# OMODRI_Gate_Driver_2.net
KiCad netlist of a schematic drawn in Altium Designer
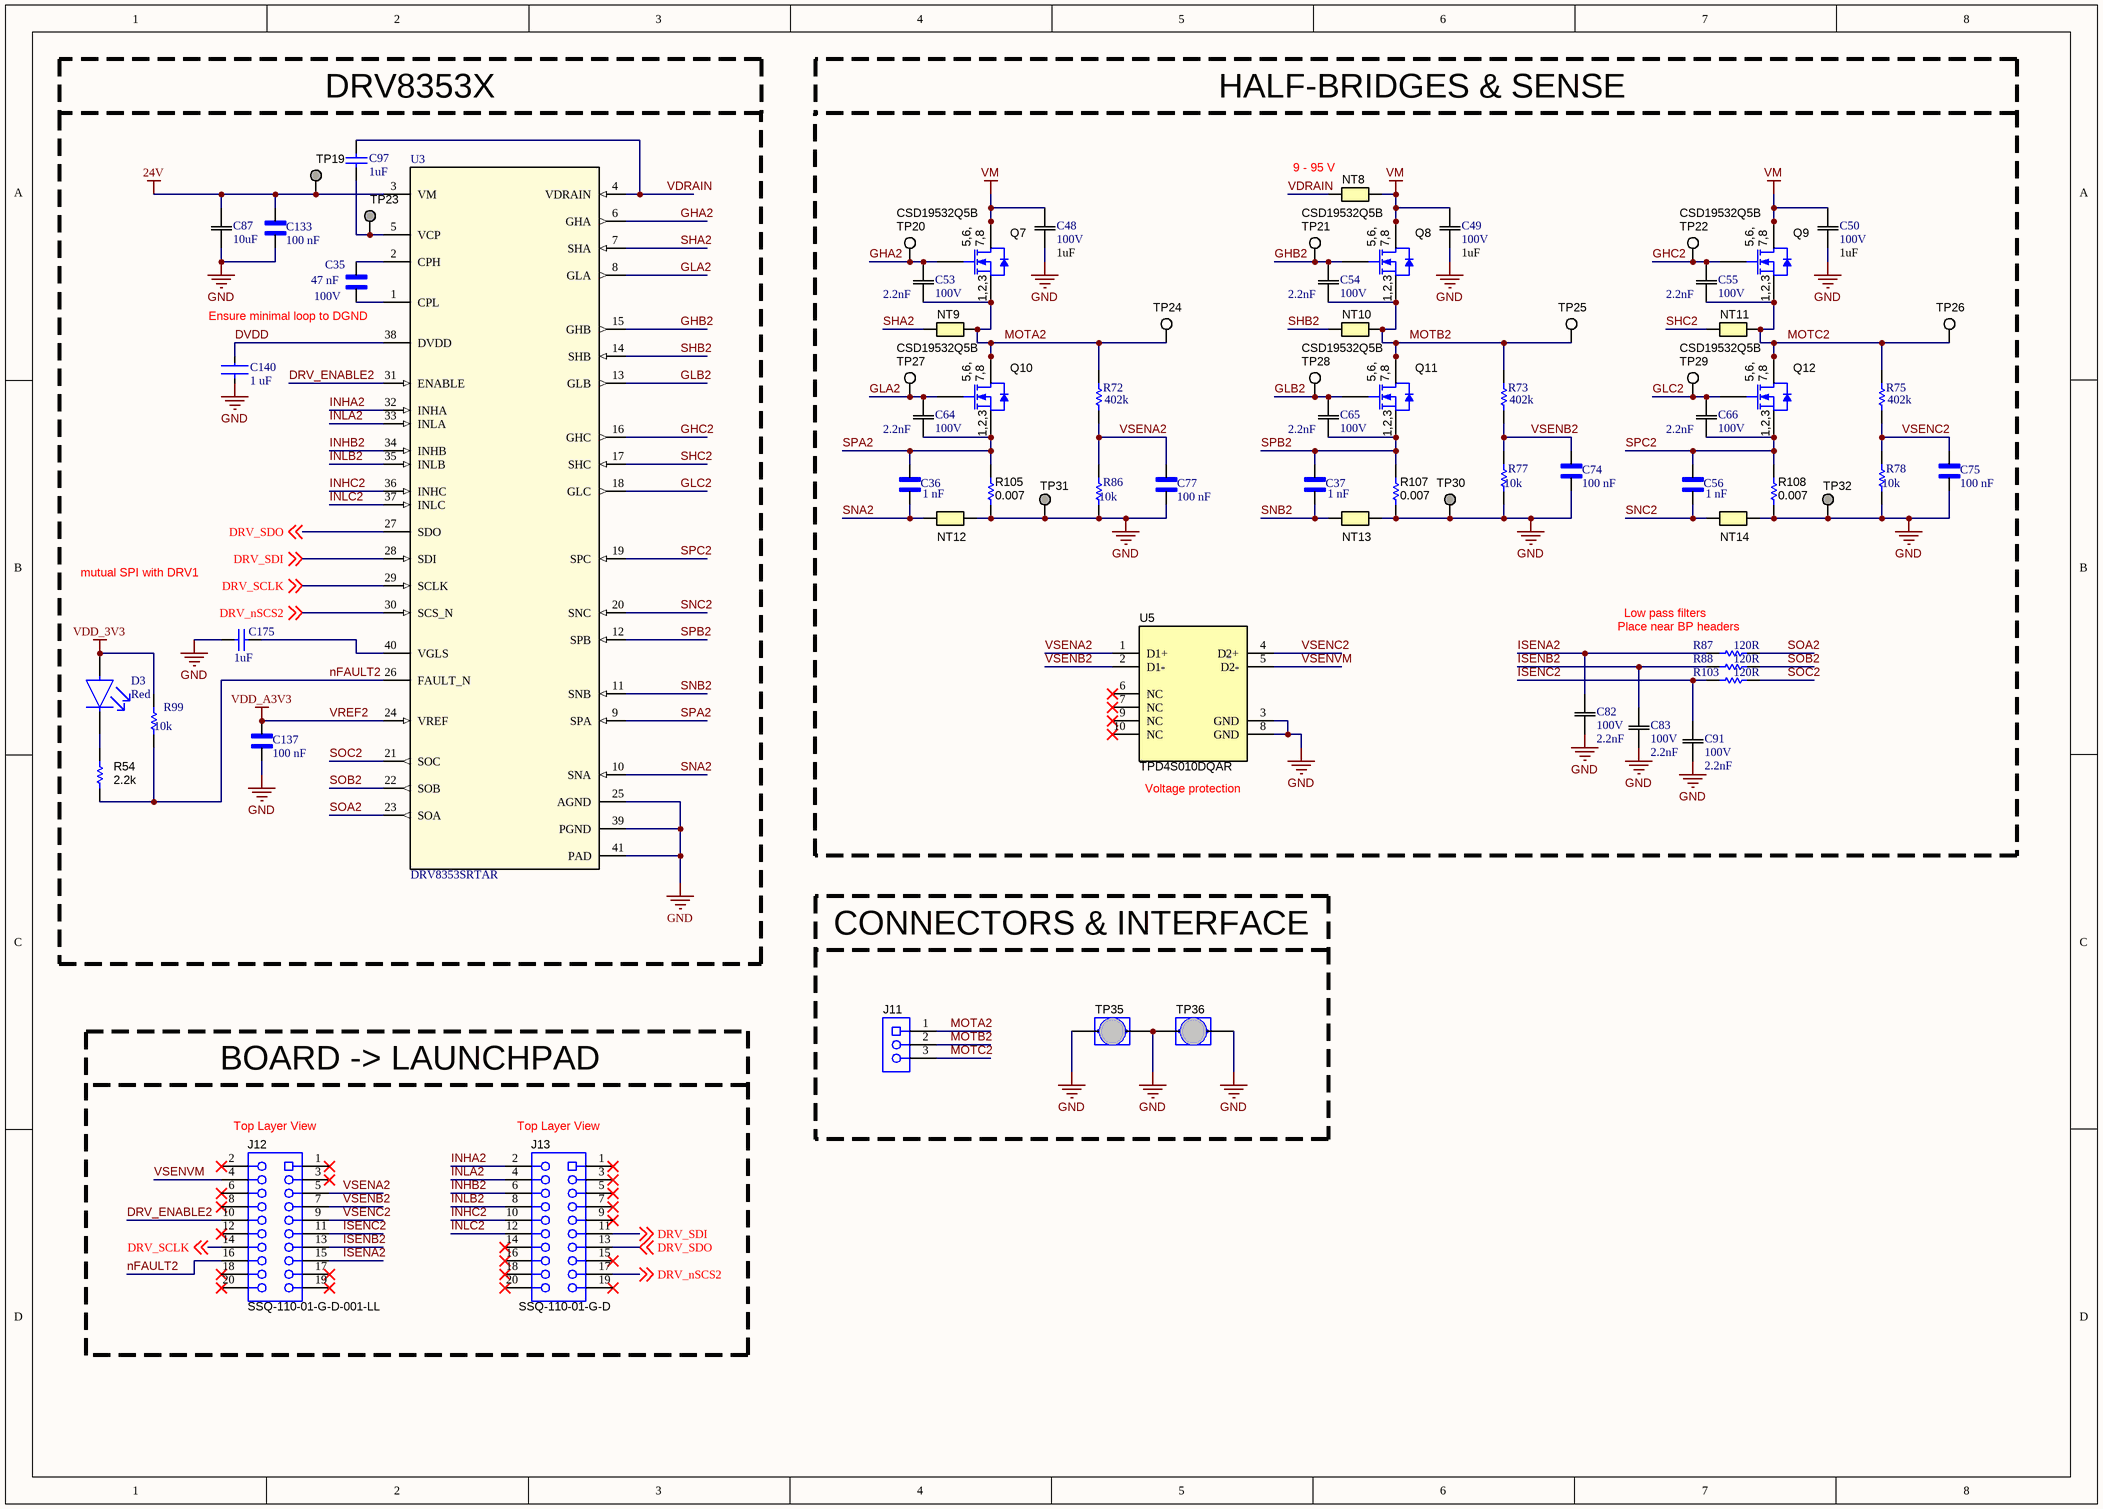
[diagram p0: OMODRI_Gate_Driver_2.SchDoc]

(export (version "E")
  (design (tool "Eeschema 10.0.6"))
  (components
    (comp (ref "C35")
      (value "47 nF")
      (footprint "CAPC1608X90N")
      (description "SMD Capacitor X8R_EIA_ with Capacitance: 47000pF Tol. 10%. Rated Voltage: 100Vdc")
      (fields
        (field (name "DIGI-KEY_PART_NUMBER") "490-GCG188R92A473KA01DCT-ND")
        (field (name "MP") "GCG188R92A473KA01D")
        (field (name "VOLTAGE") "100V")
      )
      (libsource (lib "Murata-Capacitor") (part "GCG188R92A473KA01D"))
    )
    (comp (ref "C36")
      (value "1 nF")
      (footprint "CAPC0603X33N")
      (description "SMD Capacitor X7R_EIA_ with Capacitance: 1000pF Tol. 10%. Rated Voltage: 50Vdc")
      (fields (field (name "DIGI-KEY_PART_NUMBER") "490-10682-1-ND") (field (name "MP") "GRM033R71H102KA12D"))
      (libsource (lib "Murata-CapacitorGRM") (part "GRM033R71H102KA12D"))
    )
    (comp (ref "C37")
      (value "1 nF")
      (footprint "CAPC0603X33N")
      (description "SMD Capacitor X7R_EIA_ with Capacitance: 1000pF Tol. 10%. Rated Voltage: 50Vdc")
      (fields (field (name "DIGI-KEY_PART_NUMBER") "490-10682-1-ND") (field (name "MP") "GRM033R71H102KA12D"))
      (libsource (lib "Murata-CapacitorGRM") (part "GRM033R71H102KA12D"))
    )
    (comp (ref "C48")
      (value "1uF")
      (footprint "0805_AVX")
      (description "Cap Ceramic 1uF 100V X7R 10% Pad SMD 0805 Soft Termination 125C Automotive T/R")
      (fields
        (field (name "MANUFACTURER_PART_NUMBER") "08051C102K4Z2A")
        (field (name "MANUFACTURER") "Kyocera AVX")
        (field (name "VOLTAGE") "100V")
        (field (name "COPYRIGHT") "Copyright (C) 2018 Accelerated Designs. All rights reserved")
      )
      (libsource (lib "AVX-Capacitor") (part "08051C105K4Z2A"))
    )
    (comp (ref "C49")
      (value "1uF")
      (footprint "0805_AVX")
      (description "Cap Ceramic 1uF 100V X7R 10% Pad SMD 0805 Soft Termination 125C Automotive T/R")
      (fields
        (field (name "MANUFACTURER_PART_NUMBER") "08051C102K4Z2A")
        (field (name "MANUFACTURER") "Kyocera AVX")
        (field (name "VOLTAGE") "100V")
        (field (name "COPYRIGHT") "Copyright (C) 2018 Accelerated Designs. All rights reserved")
      )
      (libsource (lib "AVX-Capacitor") (part "08051C105K4Z2A"))
    )
    (comp (ref "C50")
      (value "1uF")
      (footprint "0805_AVX")
      (description "Cap Ceramic 1uF 100V X7R 10% Pad SMD 0805 Soft Termination 125C Automotive T/R")
      (fields
        (field (name "MANUFACTURER_PART_NUMBER") "08051C102K4Z2A")
        (field (name "MANUFACTURER") "Kyocera AVX")
        (field (name "VOLTAGE") "100V")
        (field (name "COPYRIGHT") "Copyright (C) 2018 Accelerated Designs. All rights reserved")
      )
      (libsource (lib "AVX-Capacitor") (part "08051C105K4Z2A"))
    )
    (comp (ref "C53")
      (value "Part Number: C1005X8R2A222K050BA")
      (footprint "CAP_1005")
      (description "CAP CER 2200PF 100V X8R 0402")
      (fields
        (field (name "MANUFACTURER_PART_NUMBER") "C1005X8R2A222K050BA")
        (field (name "MANUFACTURER") "TDK")
        (field (name "VOLTAGE RATING (DC)") "100V")
        (field (name "CAPACITANCE") "2.2nF")
        (field (name "COPYRIGHT") "Copyright (C) 2018 Accelerated Designs. All rights reserved")
      )
      (libsource (lib "TDK-Capacitor") (part "C1005X8R2A222K05"))
    )
    (comp (ref "C54")
      (value "Part Number: C1005X8R2A222K050BA")
      (footprint "CAP_1005")
      (description "CAP CER 2200PF 100V X8R 0402")
      (fields
        (field (name "MANUFACTURER_PART_NUMBER") "C1005X8R2A222K050BA")
        (field (name "MANUFACTURER") "TDK")
        (field (name "VOLTAGE RATING (DC)") "100V")
        (field (name "CAPACITANCE") "2.2nF")
        (field (name "COPYRIGHT") "Copyright (C) 2018 Accelerated Designs. All rights reserved")
      )
      (libsource (lib "TDK-Capacitor") (part "C1005X8R2A222K05"))
    )
    (comp (ref "C55")
      (value "Part Number: C1005X8R2A222K050BA")
      (footprint "CAP_1005")
      (description "CAP CER 2200PF 100V X8R 0402")
      (fields
        (field (name "MANUFACTURER_PART_NUMBER") "C1005X8R2A222K050BA")
        (field (name "MANUFACTURER") "TDK")
        (field (name "VOLTAGE RATING (DC)") "100V")
        (field (name "CAPACITANCE") "2.2nF")
        (field (name "COPYRIGHT") "Copyright (C) 2018 Accelerated Designs. All rights reserved")
      )
      (libsource (lib "TDK-Capacitor") (part "C1005X8R2A222K05"))
    )
    (comp (ref "C56")
      (value "1 nF")
      (footprint "CAPC0603X33N")
      (description "SMD Capacitor X7R_EIA_ with Capacitance: 1000pF Tol. 10%. Rated Voltage: 50Vdc")
      (fields (field (name "DIGI-KEY_PART_NUMBER") "490-10682-1-ND") (field (name "MP") "GRM033R71H102KA12D"))
      (libsource (lib "Murata-CapacitorGRM") (part "GRM033R71H102KA12D"))
    )
    (comp (ref "C64")
      (value "Part Number: C1005X8R2A222K050BA")
      (footprint "CAP_1005")
      (description "CAP CER 2200PF 100V X8R 0402")
      (fields
        (field (name "MANUFACTURER_PART_NUMBER") "C1005X8R2A222K050BA")
        (field (name "MANUFACTURER") "TDK")
        (field (name "VOLTAGE RATING (DC)") "100V")
        (field (name "CAPACITANCE") "2.2nF")
        (field (name "COPYRIGHT") "Copyright (C) 2018 Accelerated Designs. All rights reserved")
      )
      (libsource (lib "TDK-Capacitor") (part "C1005X8R2A222K05"))
    )
    (comp (ref "C65")
      (value "Part Number: C1005X8R2A222K050BA")
      (footprint "CAP_1005")
      (description "CAP CER 2200PF 100V X8R 0402")
      (fields
        (field (name "MANUFACTURER_PART_NUMBER") "C1005X8R2A222K050BA")
        (field (name "MANUFACTURER") "TDK")
        (field (name "VOLTAGE RATING (DC)") "100V")
        (field (name "CAPACITANCE") "2.2nF")
        (field (name "COPYRIGHT") "Copyright (C) 2018 Accelerated Designs. All rights reserved")
      )
      (libsource (lib "TDK-Capacitor") (part "C1005X8R2A222K05"))
    )
    (comp (ref "C66")
      (value "Part Number: C1005X8R2A222K050BA")
      (footprint "CAP_1005")
      (description "CAP CER 2200PF 100V X8R 0402")
      (fields
        (field (name "MANUFACTURER_PART_NUMBER") "C1005X8R2A222K050BA")
        (field (name "MANUFACTURER") "TDK")
        (field (name "VOLTAGE RATING (DC)") "100V")
        (field (name "CAPACITANCE") "2.2nF")
        (field (name "COPYRIGHT") "Copyright (C) 2018 Accelerated Designs. All rights reserved")
      )
      (libsource (lib "TDK-Capacitor") (part "C1005X8R2A222K05"))
    )
    (comp (ref "C74")
      (value "100 nF")
      (footprint "CAPC0603X33N")
      (description "SMD Capacitor X5R_EIA_ with Capacitance: 0.10uF Tol. 10%. Rated Voltage: 25Vdc")
      (fields (field (name "MF") "Murata") (field (name "MP") "GRM033R61E104KE14D"))
      (libsource (lib "GRM033R61E104KE14D") (part "GRM033R61E104KE14D"))
    )
    (comp (ref "C75")
      (value "100 nF")
      (footprint "CAPC0603X33N")
      (description "SMD Capacitor X5R_EIA_ with Capacitance: 0.10uF Tol. 10%. Rated Voltage: 25Vdc")
      (fields (field (name "MF") "Murata") (field (name "MP") "GRM033R61E104KE14D"))
      (libsource (lib "GRM033R61E104KE14D") (part "GRM033R61E104KE14D"))
    )
    (comp (ref "C77")
      (value "100 nF")
      (footprint "CAPC0603X33N")
      (description "SMD Capacitor X5R_EIA_ with Capacitance: 0.10uF Tol. 10%. Rated Voltage: 25Vdc")
      (fields (field (name "MF") "Murata") (field (name "MP") "GRM033R61E104KE14D"))
      (libsource (lib "GRM033R61E104KE14D") (part "GRM033R61E104KE14D"))
    )
    (comp (ref "C82")
      (value "Part Number: C1005X8R2A222K050BA")
      (footprint "CAP_1005")
      (description "CAP CER 2200PF 100V X8R 0402")
      (fields
        (field (name "MANUFACTURER_PART_NUMBER") "C1005X8R2A222K050BA")
        (field (name "MANUFACTURER") "TDK")
        (field (name "VOLTAGE RATING (DC)") "100V")
        (field (name "CAPACITANCE") "2.2nF")
        (field (name "COPYRIGHT") "Copyright (C) 2018 Accelerated Designs. All rights reserved")
      )
      (libsource (lib "TDK-Capacitor") (part "C1005X8R2A222K05"))
    )
    (comp (ref "C83")
      (value "Part Number: C1005X8R2A222K050BA")
      (footprint "CAP_1005")
      (description "CAP CER 2200PF 100V X8R 0402")
      (fields
        (field (name "MANUFACTURER_PART_NUMBER") "C1005X8R2A222K050BA")
        (field (name "MANUFACTURER") "TDK")
        (field (name "VOLTAGE RATING (DC)") "100V")
        (field (name "CAPACITANCE") "2.2nF")
        (field (name "COPYRIGHT") "Copyright (C) 2018 Accelerated Designs. All rights reserved")
      )
      (libsource (lib "TDK-Capacitor") (part "C1005X8R2A222K05"))
    )
    (comp (ref "C87")
      (value "Part Number: CL10A106MA8NRNC")
      (footprint "CAP_CL10")
      (description "CAP CER 10UF 25V X5R 0603")
      (fields
        (field (name "MANUFACTURER_PART_NUMBER") "CL10A106MA8NRNC")
        (field (name "MANUFACTURER") "Samsung")
        (field (name "CAPACITANCE") "10uF")
        (field (name "COPYRIGHT") "Copyright (C) 2018 Accelerated Designs. All rights reserved")
      )
      (libsource (lib "Samsung-Capacitor") (part "CL10A106MA8NRNC"))
    )
    (comp (ref "C91")
      (value "Part Number: C1005X8R2A222K050BA")
      (footprint "CAP_1005")
      (description "CAP CER 2200PF 100V X8R 0402")
      (fields
        (field (name "MANUFACTURER_PART_NUMBER") "C1005X8R2A222K050BA")
        (field (name "MANUFACTURER") "TDK")
        (field (name "VOLTAGE RATING (DC)") "100V")
        (field (name "CAPACITANCE") "2.2nF")
        (field (name "COPYRIGHT") "Copyright (C) 2018 Accelerated Designs. All rights reserved")
      )
      (libsource (lib "TDK-Capacitor") (part "C1005X8R2A222K05"))
    )
    (comp (ref "C97")
      (value "1uF")
      (footprint "CAPC1005X55X25ML05T10")
      (fields (field (name "PART NUMBER") "GRM155R61C105KA12D") (field (name "MANUFACTURER") "Murata"))
      (libsource (lib "Altium Content Vault") (part "CAP"))
    )
    (comp (ref "C133")
      (value "100 nF")
      (footprint "CAPC0603X33N")
      (description "SMD Capacitor X5R_EIA_ with Capacitance: 0.10uF Tol. 10%. Rated Voltage: 25Vdc")
      (fields (field (name "MF") "Murata") (field (name "MP") "GRM033R61E104KE14D"))
      (libsource (lib "GRM033R61E104KE14D") (part "GRM033R61E104KE14D"))
    )
    (comp (ref "C137")
      (value "100 nF")
      (footprint "CAPC0603X33N")
      (description "SMD Capacitor X5R_EIA_ with Capacitance: 0.10uF Tol. 10%. Rated Voltage: 25Vdc")
      (fields (field (name "MF") "Murata") (field (name "MP") "GRM033R61E104KE14D"))
      (libsource (lib "GRM033R61E104KE14D") (part "GRM033R61E104KE14D"))
    )
    (comp (ref "C140")
      (value "1 uF")
      (footprint "FP-CC0201-BA-MFG")
      (description "CAP CER 1UF 6.3V X5R 0201")
      (fields (field (name "TOLERANCE") "0.2") (field (name "MANUFACTURER") "Yageo"))
      (libsource (lib "Altium Content Vault") (part "11868f565c42a9108669ba33697ecf6"))
    )
    (comp (ref "C175")
      (value "1uF")
      (footprint "CAPC1005X55X25ML05T10")
      (fields (field (name "PART NUMBER") "GRM155R61C105KA12D") (field (name "MANUFACTURER") "Murata"))
      (libsource (lib "Altium Content Vault") (part "CAP"))
    )
    (comp (ref "D3")
      (value "SML-P11UTT86R")
      (footprint "FP-SML-P1-MFG")
      (description "LED, PICOLED, Red, SMD, 1 mA, 1.8 V, 621 nm")
      (fields
        (field (name "MANUFACTURER PART NUMBER") "SML-P11VTT86R")
        (field (name "OCTOPART") "https://octopart.com/sml-p11vtt86r-rohm-34112314")
        (field (name "COLOUR") "Red")
      )
      (libsource (lib "LED") (part "SML-P11UTT86R"))
    )
    (comp (ref "J11")
      (value "1904150")
      (footprint "Phoenix_1904150")
      (description "Terminal Block, 9.52mm, 3x1, R/A, TH")
      (fields (field (name "MANUFACTURER") "Phoenix Contact") (field (name "PUBLISHER") "Texas Instruments"))
      (libsource (lib "Altium Vault - TI") (part "Receptacle_3x1"))
    )
    (comp (ref "J12")
      (value "SSQ-110-01-G-D-001-LL")
      (footprint "Samtec_SSQ-110-01-x-D-001-LL")
      (description "Receptacle, 2.54mm, 10x2, Gold, TH")
      (fields (field (name "MANUFACTURER") "Samtec"))
      (libsource (lib "Altium Vault - TI") (part "Receptacle_10x2"))
    )
    (comp (ref "J13")
      (value "SSQ-110-01-G-D")
      (footprint "Samtec_SSQ-110-01-x-D")
      (description "Receptacle, 2.54mm, 10x2, Gold, TH")
      (fields (field (name "MANUFACTURER") "Samtec"))
      (libsource (lib "Altium Vault - TI") (part "CMP-0082605-1"))
    )
    (comp (ref "NT8")
      (value "Net-Tie")
      (footprint "Net-Tie_50milWide_30milLong")
      (description "Single point connection between nets.")
      (libsource (lib "Altium Vault - TI") (part "Net-Tie"))
    )
    (comp (ref "NT9")
      (value "Net-Tie")
      (footprint "Net-Tie_10mil")
      (description "Single point connection between nets.")
      (libsource (lib "Altium Vault - TI") (part "Net-Tie"))
    )
    (comp (ref "NT10")
      (value "Net-Tie")
      (footprint "Net-Tie_10mil")
      (description "Single point connection between nets.")
      (libsource (lib "Altium Vault - TI") (part "Net-Tie"))
    )
    (comp (ref "NT11")
      (value "Net-Tie")
      (footprint "Net-Tie_10mil")
      (description "Single point connection between nets.")
      (libsource (lib "Altium Vault - TI") (part "Net-Tie"))
    )
    (comp (ref "NT12")
      (value "Net-Tie")
      (footprint "Net-Tie_10mil")
      (description "Single point connection between nets.")
      (libsource (lib "Altium Vault - TI") (part "Net-Tie"))
    )
    (comp (ref "NT13")
      (value "Net-Tie")
      (footprint "Net-Tie_10mil")
      (description "Single point connection between nets.")
      (libsource (lib "Altium Vault - TI") (part "Net-Tie"))
    )
    (comp (ref "NT14")
      (value "Net-Tie")
      (footprint "Net-Tie_10mil")
      (description "Single point connection between nets.")
      (libsource (lib "Altium Vault - TI") (part "Net-Tie"))
    )
    (comp (ref "Q7")
      (value "CSD19532Q5B")
      (footprint "DNK0008A")
      (description "MOSFET, N-CH, 100 V, 17 A, DNK0008A (VSON-CLIP-8)")
      (fields (field (name "MANUFACTURER") "Texas Instruments"))
      (libsource (lib "Altium Vault - TI") (part "MOSFET_N_D56789G4S123"))
    )
    (comp (ref "Q8")
      (value "CSD19532Q5B")
      (footprint "DNK0008A")
      (description "MOSFET, N-CH, 100 V, 17 A, DNK0008A (VSON-CLIP-8)")
      (fields (field (name "MANUFACTURER") "Texas Instruments"))
      (libsource (lib "Altium Vault - TI") (part "MOSFET_N_D56789G4S123"))
    )
    (comp (ref "Q9")
      (value "CSD19532Q5B")
      (footprint "DNK0008A")
      (description "MOSFET, N-CH, 100 V, 17 A, DNK0008A (VSON-CLIP-8)")
      (fields (field (name "MANUFACTURER") "Texas Instruments"))
      (libsource (lib "Altium Vault - TI") (part "MOSFET_N_D56789G4S123"))
    )
    (comp (ref "Q10")
      (value "CSD19532Q5B")
      (footprint "DNK0008A")
      (description "MOSFET, N-CH, 100 V, 17 A, DNK0008A (VSON-CLIP-8)")
      (fields (field (name "MANUFACTURER") "Texas Instruments"))
      (libsource (lib "Altium Vault - TI") (part "MOSFET_N_D56789G4S123"))
    )
    (comp (ref "Q11")
      (value "CSD19532Q5B")
      (footprint "DNK0008A")
      (description "MOSFET, N-CH, 100 V, 17 A, DNK0008A (VSON-CLIP-8)")
      (fields (field (name "MANUFACTURER") "Texas Instruments"))
      (libsource (lib "Altium Vault - TI") (part "MOSFET_N_D56789G4S123"))
    )
    (comp (ref "Q12")
      (value "CSD19532Q5B")
      (footprint "DNK0008A")
      (description "MOSFET, N-CH, 100 V, 17 A, DNK0008A (VSON-CLIP-8)")
      (fields (field (name "MANUFACTURER") "Texas Instruments"))
      (libsource (lib "Altium Vault - TI") (part "MOSFET_N_D56789G4S123"))
    )
    (comp (ref "R54")
      (value "CRCW04022K20JNED")
      (footprint "0402")
      (description "RES, 2.2 k, 5%, 0.063 W, AEC-Q200 Grade 0, 0402")
      (fields (field (name "MANUFACTURER") "Vishay-Dale") (field (name "VALUEDISPLAYED") "2.2k"))
      (libsource (lib "Altium Vault - TI") (part "Resistor"))
    )
    (comp (ref "R72")
      (value "ERJ-2RKF4023X")
      (footprint "RESC1005X40X25LL05T05")
      (description "RES SMD 402K OHM 1% 1/10W 0402")
      (fields (field (name "MANUFACTURER") "Panasonic") (field (name "RESISTANCE") "402k"))
      (libsource (lib "Altium Content Vault") (part "RES"))
    )
    (comp (ref "R73")
      (value "ERJ-2RKF4023X")
      (footprint "RESC1005X40X25LL05T05")
      (description "RES SMD 402K OHM 1% 1/10W 0402")
      (fields (field (name "MANUFACTURER") "Panasonic") (field (name "RESISTANCE") "402k"))
      (libsource (lib "Altium Content Vault") (part "RES"))
    )
    (comp (ref "R75")
      (value "ERJ-2RKF4023X")
      (footprint "RESC1005X40X25LL05T05")
      (description "RES SMD 402K OHM 1% 1/10W 0402")
      (fields (field (name "MANUFACTURER") "Panasonic") (field (name "RESISTANCE") "402k"))
      (libsource (lib "Altium Content Vault") (part "RES"))
    )
    (comp (ref "R77")
      (value "ERJ2RKF1002X")
      (footprint "RESC1005X40X25LL05T05")
      (description "Chip Resistor, 10 KOhm, +/- 1%, 0.1 W, -55 to 155 degC, 0402 (1005 Metric), RoHS, Tape and Reel")
      (fields
        (field (name "RESISTANCE") "10k")
        (field (name "TOLERANCE") "1%")
        (field (name "MANUFACTURER") "Panasonic")
      )
      (libsource (lib "Altium Content Vault") (part "RES-2"))
    )
    (comp (ref "R78")
      (value "ERJ2RKF1002X")
      (footprint "RESC1005X40X25LL05T05")
      (description "Chip Resistor, 10 KOhm, +/- 1%, 0.1 W, -55 to 155 degC, 0402 (1005 Metric), RoHS, Tape and Reel")
      (fields
        (field (name "RESISTANCE") "10k")
        (field (name "TOLERANCE") "1%")
        (field (name "MANUFACTURER") "Panasonic")
      )
      (libsource (lib "Altium Content Vault") (part "RES-2"))
    )
    (comp (ref "R86")
      (value "ERJ2RKF1002X")
      (footprint "RESC1005X40X25LL05T05")
      (description "Chip Resistor, 10 KOhm, +/- 1%, 0.1 W, -55 to 155 degC, 0402 (1005 Metric), RoHS, Tape and Reel")
      (fields
        (field (name "RESISTANCE") "10k")
        (field (name "TOLERANCE") "1%")
        (field (name "MANUFACTURER") "Panasonic")
      )
      (libsource (lib "Altium Content Vault") (part "RES-2"))
    )
    (comp (ref "R87")
      (value "CRCW0402120RJNEDHP")
      (footprint "RESC1005X40X25ML05T10")
      (description "RES SMD 120 OHM 5% 1/5W 0402")
      (fields
        (field (name "MANUFACTURER") "Vishay Dale")
        (field (name "TOLERANCE") "5%")
        (field (name "RESISTANCE") "120R")
      )
      (libsource (lib "Vishay-Resistor") (part "CRCW0402120RJNEDHP"))
    )
    (comp (ref "R88")
      (value "CRCW0402120RJNEDHP")
      (footprint "RESC1005X40X25ML05T10")
      (description "RES SMD 120 OHM 5% 1/5W 0402")
      (fields
        (field (name "MANUFACTURER") "Vishay Dale")
        (field (name "TOLERANCE") "5%")
        (field (name "RESISTANCE") "120R")
      )
      (libsource (lib "Vishay-Resistor") (part "CRCW0402120RJNEDHP"))
    )
    (comp (ref "R99")
      (value "ERJ2RKF1002X")
      (footprint "RESC1005X40X25LL05T05")
      (description "Chip Resistor, 10 KOhm, +/- 1%, 0.1 W, -55 to 155 degC, 0402 (1005 Metric), RoHS, Tape and Reel")
      (fields
        (field (name "RESISTANCE") "10k")
        (field (name "TOLERANCE") "1%")
        (field (name "MANUFACTURER") "Panasonic")
      )
      (libsource (lib "Altium Content Vault") (part "RES-2"))
    )
    (comp (ref "R103")
      (value "CRCW0402120RJNEDHP")
      (footprint "RESC1005X40X25ML05T10")
      (description "RES SMD 120 OHM 5% 1/5W 0402")
      (fields
        (field (name "MANUFACTURER") "Vishay Dale")
        (field (name "TOLERANCE") "5%")
        (field (name "RESISTANCE") "120R")
      )
      (libsource (lib "Vishay-Resistor") (part "CRCW0402120RJNEDHP"))
    )
    (comp (ref "R105")
      (value "CRE2512-FZ-R007E-3")
      (footprint "CRE2512-R5_R9")
      (description "RES, 0.007, 1%, 3 W, AEC-Q200 Grade 0, 2512")
      (fields
        (field (name "VALUEDISPLAYED") "0.007")
        (field (name "MANUFACTURER") "Bourns")
        (field (name "PUBLISHER") "Texas Instruments")
      )
      (libsource (lib "Altium Vault - TI") (part "Resistor"))
    )
    (comp (ref "R107")
      (value "CRE2512-FZ-R007E-3")
      (footprint "CRE2512-R5_R9")
      (description "RES, 0.007, 1%, 3 W, AEC-Q200 Grade 0, 2512")
      (fields
        (field (name "VALUEDISPLAYED") "0.007")
        (field (name "MANUFACTURER") "Bourns")
        (field (name "PUBLISHER") "Texas Instruments")
      )
      (libsource (lib "Altium Vault - TI") (part "Resistor"))
    )
    (comp (ref "R108")
      (value "CRE2512-FZ-R007E-3")
      (footprint "CRE2512-R5_R9")
      (description "RES, 0.007, 1%, 3 W, AEC-Q200 Grade 0, 2512")
      (fields
        (field (name "VALUEDISPLAYED") "0.007")
        (field (name "MANUFACTURER") "Bourns")
        (field (name "PUBLISHER") "Texas Instruments")
      )
      (libsource (lib "Altium Vault - TI") (part "Resistor"))
    )
    (comp (ref "TP19")
      (value "TP_SM_1MM")
      (footprint "TP_SM_1MM")
      (description "1mm Test Point, SMT")
      (fields (field (name "MANUFACTURER") "Any") (field (name "PUBLISHER") "Texas Instruments"))
      (libsource (lib "Altium Vault - TI") (part "TESTPOINT"))
    )
    (comp (ref "TP20")
      (value "5002")
      (footprint "Keystone5002")
      (description "Test Point, Miniature, White, TH")
      (fields (field (name "MANUFACTURER") "Keystone") (field (name "PUBLISHER") "Texas Instruments"))
      (libsource (lib "Altium Vault - TI") (part "5002"))
    )
    (comp (ref "TP21")
      (value "5002")
      (footprint "Keystone5002")
      (description "Test Point, Miniature, White, TH")
      (fields (field (name "MANUFACTURER") "Keystone") (field (name "PUBLISHER") "Texas Instruments"))
      (libsource (lib "Altium Vault - TI") (part "5002"))
    )
    (comp (ref "TP22")
      (value "5002")
      (footprint "Keystone5002")
      (description "Test Point, Miniature, White, TH")
      (fields (field (name "MANUFACTURER") "Keystone") (field (name "PUBLISHER") "Texas Instruments"))
      (libsource (lib "Altium Vault - TI") (part "5002"))
    )
    (comp (ref "TP23")
      (value "TP_SM_1MM")
      (footprint "TP_SM_1MM")
      (description "1mm Test Point, SMT")
      (fields (field (name "MANUFACTURER") "Any") (field (name "PUBLISHER") "Texas Instruments"))
      (libsource (lib "Altium Vault - TI") (part "TESTPOINT"))
    )
    (comp (ref "TP24")
      (value "5002")
      (footprint "Keystone5002")
      (description "Test Point, Miniature, White, TH")
      (fields (field (name "MANUFACTURER") "Keystone") (field (name "PUBLISHER") "Texas Instruments"))
      (libsource (lib "Altium Vault - TI") (part "5002"))
    )
    (comp (ref "TP25")
      (value "5002")
      (footprint "Keystone5002")
      (description "Test Point, Miniature, White, TH")
      (fields (field (name "MANUFACTURER") "Keystone") (field (name "PUBLISHER") "Texas Instruments"))
      (libsource (lib "Altium Vault - TI") (part "5002"))
    )
    (comp (ref "TP26")
      (value "5002")
      (footprint "Keystone5002")
      (description "Test Point, Miniature, White, TH")
      (fields (field (name "MANUFACTURER") "Keystone") (field (name "PUBLISHER") "Texas Instruments"))
      (libsource (lib "Altium Vault - TI") (part "5002"))
    )
    (comp (ref "TP27")
      (value "5002")
      (footprint "Keystone5002")
      (description "Test Point, Miniature, White, TH")
      (fields (field (name "MANUFACTURER") "Keystone") (field (name "PUBLISHER") "Texas Instruments"))
      (libsource (lib "Altium Vault - TI") (part "5002"))
    )
    (comp (ref "TP28")
      (value "5002")
      (footprint "Keystone5002")
      (description "Test Point, Miniature, White, TH")
      (fields (field (name "MANUFACTURER") "Keystone") (field (name "PUBLISHER") "Texas Instruments"))
      (libsource (lib "Altium Vault - TI") (part "5002"))
    )
    (comp (ref "TP29")
      (value "5002")
      (footprint "Keystone5002")
      (description "Test Point, Miniature, White, TH")
      (fields (field (name "MANUFACTURER") "Keystone") (field (name "PUBLISHER") "Texas Instruments"))
      (libsource (lib "Altium Vault - TI") (part "5002"))
    )
    (comp (ref "TP30")
      (value "TP_SM_1MM")
      (footprint "TP_SM_1MM")
      (description "1mm Test Point, SMT")
      (fields (field (name "MANUFACTURER") "Any") (field (name "PUBLISHER") "Texas Instruments"))
      (libsource (lib "Altium Vault - TI") (part "TESTPOINT"))
    )
    (comp (ref "TP31")
      (value "TP_SM_1MM")
      (footprint "TP_SM_1MM")
      (description "1mm Test Point, SMT")
      (fields (field (name "MANUFACTURER") "Any") (field (name "PUBLISHER") "Texas Instruments"))
      (libsource (lib "Altium Vault - TI") (part "TESTPOINT"))
    )
    (comp (ref "TP32")
      (value "TP_SM_1MM")
      (footprint "TP_SM_1MM")
      (description "1mm Test Point, SMT")
      (fields (field (name "MANUFACTURER") "Any") (field (name "PUBLISHER") "Texas Instruments"))
      (libsource (lib "Altium Vault - TI") (part "TESTPOINT"))
    )
    (comp (ref "TP35")
      (value "D3082-05")
      (footprint "Harwin_D3082-05")
      (description "1mm Uninsulated Shorting Plug, 10.16mm spacing, TH")
      (fields (field (name "MANUFACTURER") "Harwin") (field (name "PUBLISHER") "Texas Instruments"))
      (libsource (lib "Altium Vault - TI") (part "Jumper_2p"))
    )
    (comp (ref "TP36")
      (value "D3082-05")
      (footprint "Harwin_D3082-05")
      (description "1mm Uninsulated Shorting Plug, 10.16mm spacing, TH")
      (fields (field (name "MANUFACTURER") "Harwin") (field (name "PUBLISHER") "Texas Instruments"))
      (libsource (lib "Altium Vault - TI") (part "Jumper_2p"))
    )
    (comp (ref "U3")
      (value "DRV8353SRTAR")
      (footprint "RTA0040B")
      (fields (field (name "MANUFACTURER") "Texas Instruments"))
      (libsource (lib "Texas_Instruments") (part "DRV8353SRTAR"))
    )
    (comp (ref "U5")
      (value "TPD4S010DQAR")
      (footprint "DQA0010A")
      (fields (field (name "MANUFACTURER") "Texas Instruments") (field (name "PARTNUMBER") "TPD4S010DQAR"))
      (libsource (lib "Altium Vault - TI") (part "TI-TPD4S010-SON_DQA-10"))
    )
  )
  (nets
    (net (code "1") (name "/DRV_ENABLE2") (class "Default")
      (node (ref "J12") (pin "10") (pinfunction "10_10") (pintype "passive"))
      (node (ref "U3") (pin "31") (pinfunction "ENABLE_31") (pintype "input"))
    )
    (net (code "2") (name "/DVDD") (class "Default")
      (node (ref "C140") (pin "2") (pinfunction "2_2") (pintype "passive"))
      (node (ref "U3") (pin "38") (pinfunction "DVDD_38") (pintype "power_in"))
    )
    (net (code "3") (name "/GHA2") (class "Default")
      (node (ref "C53") (pin "2") (pinfunction "2_2") (pintype "passive"))
      (node (ref "Q7") (pin "4") (pinfunction "G_4") (pintype "passive"))
      (node (ref "TP20") (pin "1") (pintype "passive"))
      (node (ref "U3") (pin "6") (pinfunction "GHA_6") (pintype "output"))
    )
    (net (code "4") (name "/GHB2") (class "Default")
      (node (ref "C54") (pin "2") (pinfunction "2_2") (pintype "passive"))
      (node (ref "Q8") (pin "4") (pinfunction "G_4") (pintype "passive"))
      (node (ref "TP21") (pin "1") (pintype "passive"))
      (node (ref "U3") (pin "15") (pinfunction "GHB_15") (pintype "output"))
    )
    (net (code "5") (name "/GHC2") (class "Default")
      (node (ref "C55") (pin "2") (pinfunction "2_2") (pintype "passive"))
      (node (ref "Q9") (pin "4") (pinfunction "G_4") (pintype "passive"))
      (node (ref "TP22") (pin "1") (pintype "passive"))
      (node (ref "U3") (pin "16") (pinfunction "GHC_16") (pintype "output"))
    )
    (net (code "6") (name "/GLA2") (class "Default")
      (node (ref "C64") (pin "2") (pinfunction "2_2") (pintype "passive"))
      (node (ref "Q10") (pin "4") (pinfunction "G_4") (pintype "passive"))
      (node (ref "TP27") (pin "1") (pintype "passive"))
      (node (ref "U3") (pin "8") (pinfunction "GLA_8") (pintype "output"))
    )
    (net (code "7") (name "/GLB2") (class "Default")
      (node (ref "C65") (pin "2") (pinfunction "2_2") (pintype "passive"))
      (node (ref "Q11") (pin "4") (pinfunction "G_4") (pintype "passive"))
      (node (ref "TP28") (pin "1") (pintype "passive"))
      (node (ref "U3") (pin "13") (pinfunction "GLB_13") (pintype "output"))
    )
    (net (code "8") (name "/GLC2") (class "Default")
      (node (ref "C66") (pin "2") (pinfunction "2_2") (pintype "passive"))
      (node (ref "Q12") (pin "4") (pinfunction "G_4") (pintype "passive"))
      (node (ref "TP29") (pin "1") (pintype "passive"))
      (node (ref "U3") (pin "18") (pinfunction "GLC_18") (pintype "output"))
    )
    (net (code "9") (name "/INHA2") (class "Default")
      (node (ref "J13") (pin "2") (pinfunction "2_2") (pintype "passive"))
      (node (ref "U3") (pin "32") (pinfunction "INHA_32") (pintype "input"))
    )
    (net (code "10") (name "/INHB2") (class "Default")
      (node (ref "J13") (pin "6") (pinfunction "6_6") (pintype "passive"))
      (node (ref "U3") (pin "34") (pinfunction "INHB_34") (pintype "input"))
    )
    (net (code "11") (name "/INHC2") (class "Default")
      (node (ref "J13") (pin "10") (pinfunction "10_10") (pintype "passive"))
      (node (ref "U3") (pin "36") (pinfunction "INHC_36") (pintype "input"))
    )
    (net (code "12") (name "/INLA2") (class "Default")
      (node (ref "J13") (pin "4") (pinfunction "4_4") (pintype "passive"))
      (node (ref "U3") (pin "33") (pinfunction "INLA_33") (pintype "input"))
    )
    (net (code "13") (name "/INLB2") (class "Default")
      (node (ref "J13") (pin "8") (pinfunction "8_8") (pintype "passive"))
      (node (ref "U3") (pin "35") (pinfunction "INLB_35") (pintype "input"))
    )
    (net (code "14") (name "/INLC2") (class "Default")
      (node (ref "J13") (pin "12") (pinfunction "12_12") (pintype "passive"))
      (node (ref "U3") (pin "37") (pinfunction "INLC_37") (pintype "input"))
    )
    (net (code "15") (name "/ISENA2") (class "Default")
      (node (ref "C82") (pin "2") (pinfunction "2_2") (pintype "passive"))
      (node (ref "J12") (pin "15") (pinfunction "15_15") (pintype "passive"))
      (node (ref "R87") (pin "2") (pinfunction "2_2") (pintype "passive"))
    )
    (net (code "16") (name "/ISENB2") (class "Default")
      (node (ref "C83") (pin "2") (pinfunction "2_2") (pintype "passive"))
      (node (ref "J12") (pin "13") (pinfunction "13_13") (pintype "passive"))
      (node (ref "R88") (pin "2") (pinfunction "2_2") (pintype "passive"))
    )
    (net (code "17") (name "/ISENC2") (class "Default")
      (node (ref "C91") (pin "2") (pinfunction "2_2") (pintype "passive"))
      (node (ref "J12") (pin "11") (pinfunction "11_11") (pintype "passive"))
      (node (ref "R103") (pin "2") (pinfunction "2_2") (pintype "passive"))
    )
    (net (code "18") (name "/MOTA2") (class "Default")
      (node (ref "C53") (pin "1") (pinfunction "1_1") (pintype "passive"))
      (node (ref "J11") (pin "1") (pinfunction "1_1") (pintype "passive"))
      (node (ref "NT9") (pin "2") (pinfunction "2_2") (pintype "passive"))
      (node (ref "Q10") (pin "5") (pinfunction "D_5") (pintype "passive"))
      (node (ref "Q10") (pin "6") (pinfunction "D_6") (pintype "passive"))
      (node (ref "Q10") (pin "7") (pinfunction "D_7") (pintype "passive"))
      (node (ref "Q10") (pin "8") (pinfunction "D_8") (pintype "passive"))
      (node (ref "Q10") (pin "9") (pinfunction "D_9") (pintype "passive"))
      (node (ref "Q7") (pin "1") (pinfunction "S_1") (pintype "passive"))
      (node (ref "Q7") (pin "2") (pinfunction "S_2") (pintype "passive"))
      (node (ref "Q7") (pin "3") (pinfunction "S_3") (pintype "passive"))
      (node (ref "R72") (pin "2") (pinfunction "2_2") (pintype "passive"))
      (node (ref "TP24") (pin "1") (pintype "passive"))
    )
    (net (code "19") (name "/MOTB2") (class "Default")
      (node (ref "C54") (pin "1") (pinfunction "1_1") (pintype "passive"))
      (node (ref "J11") (pin "2") (pinfunction "2_2") (pintype "passive"))
      (node (ref "NT10") (pin "2") (pinfunction "2_2") (pintype "passive"))
      (node (ref "Q11") (pin "5") (pinfunction "D_5") (pintype "passive"))
      (node (ref "Q11") (pin "6") (pinfunction "D_6") (pintype "passive"))
      (node (ref "Q11") (pin "7") (pinfunction "D_7") (pintype "passive"))
      (node (ref "Q11") (pin "8") (pinfunction "D_8") (pintype "passive"))
      (node (ref "Q11") (pin "9") (pinfunction "D_9") (pintype "passive"))
      (node (ref "Q8") (pin "1") (pinfunction "S_1") (pintype "passive"))
      (node (ref "Q8") (pin "2") (pinfunction "S_2") (pintype "passive"))
      (node (ref "Q8") (pin "3") (pinfunction "S_3") (pintype "passive"))
      (node (ref "R73") (pin "2") (pinfunction "2_2") (pintype "passive"))
      (node (ref "TP25") (pin "1") (pintype "passive"))
    )
    (net (code "20") (name "/MOTC2") (class "Default")
      (node (ref "C55") (pin "1") (pinfunction "1_1") (pintype "passive"))
      (node (ref "J11") (pin "3") (pinfunction "3_3") (pintype "passive"))
      (node (ref "NT11") (pin "2") (pinfunction "2_2") (pintype "passive"))
      (node (ref "Q12") (pin "5") (pinfunction "D_5") (pintype "passive"))
      (node (ref "Q12") (pin "6") (pinfunction "D_6") (pintype "passive"))
      (node (ref "Q12") (pin "7") (pinfunction "D_7") (pintype "passive"))
      (node (ref "Q12") (pin "8") (pinfunction "D_8") (pintype "passive"))
      (node (ref "Q12") (pin "9") (pinfunction "D_9") (pintype "passive"))
      (node (ref "Q9") (pin "1") (pinfunction "S_1") (pintype "passive"))
      (node (ref "Q9") (pin "2") (pinfunction "S_2") (pintype "passive"))
      (node (ref "Q9") (pin "3") (pinfunction "S_3") (pintype "passive"))
      (node (ref "R75") (pin "2") (pinfunction "2_2") (pintype "passive"))
      (node (ref "TP26") (pin "1") (pintype "passive"))
    )
    (net (code "21") (name "/SHA2") (class "Default")
      (node (ref "NT9") (pin "1") (pinfunction "1_1") (pintype "passive"))
      (node (ref "U3") (pin "7") (pinfunction "SHA_7") (pintype "input"))
    )
    (net (code "22") (name "/SHB2") (class "Default")
      (node (ref "NT10") (pin "1") (pinfunction "1_1") (pintype "passive"))
      (node (ref "U3") (pin "14") (pinfunction "SHB_14") (pintype "input"))
    )
    (net (code "23") (name "/SHC2") (class "Default")
      (node (ref "NT11") (pin "1") (pinfunction "1_1") (pintype "passive"))
      (node (ref "U3") (pin "17") (pinfunction "SHC_17") (pintype "input"))
    )
    (net (code "24") (name "/SNA2") (class "Default")
      (node (ref "C36") (pin "1") (pinfunction "1_1") (pintype "passive"))
      (node (ref "NT12") (pin "1") (pinfunction "1_1") (pintype "passive"))
      (node (ref "U3") (pin "10") (pinfunction "SNA_10") (pintype "input"))
    )
    (net (code "25") (name "/SNB2") (class "Default")
      (node (ref "C37") (pin "1") (pinfunction "1_1") (pintype "passive"))
      (node (ref "NT13") (pin "1") (pinfunction "1_1") (pintype "passive"))
      (node (ref "U3") (pin "11") (pinfunction "SNB_11") (pintype "input"))
    )
    (net (code "26") (name "/SNC2") (class "Default")
      (node (ref "C56") (pin "1") (pinfunction "1_1") (pintype "passive"))
      (node (ref "NT14") (pin "1") (pinfunction "1_1") (pintype "passive"))
      (node (ref "U3") (pin "20") (pinfunction "SNC_20") (pintype "input"))
    )
    (net (code "27") (name "/SOA2") (class "Default")
      (node (ref "R87") (pin "1") (pinfunction "1_1") (pintype "passive"))
      (node (ref "U3") (pin "23") (pinfunction "SOA_23") (pintype "output"))
    )
    (net (code "28") (name "/SOB2") (class "Default")
      (node (ref "R88") (pin "1") (pinfunction "1_1") (pintype "passive"))
      (node (ref "U3") (pin "22") (pinfunction "SOB_22") (pintype "output"))
    )
    (net (code "29") (name "/SOC2") (class "Default")
      (node (ref "R103") (pin "1") (pinfunction "1_1") (pintype "passive"))
      (node (ref "U3") (pin "21") (pinfunction "SOC_21") (pintype "output"))
    )
    (net (code "30") (name "/SPA2") (class "Default")
      (node (ref "C36") (pin "2") (pinfunction "2_2") (pintype "passive"))
      (node (ref "C64") (pin "1") (pinfunction "1_1") (pintype "passive"))
      (node (ref "Q10") (pin "1") (pinfunction "S_1") (pintype "passive"))
      (node (ref "Q10") (pin "2") (pinfunction "S_2") (pintype "passive"))
      (node (ref "Q10") (pin "3") (pinfunction "S_3") (pintype "passive"))
      (node (ref "R105") (pin "2") (pinfunction "2_2") (pintype "passive"))
      (node (ref "U3") (pin "9") (pinfunction "SPA_9") (pintype "input"))
    )
    (net (code "31") (name "/SPB2") (class "Default")
      (node (ref "C37") (pin "2") (pinfunction "2_2") (pintype "passive"))
      (node (ref "C65") (pin "1") (pinfunction "1_1") (pintype "passive"))
      (node (ref "Q11") (pin "1") (pinfunction "S_1") (pintype "passive"))
      (node (ref "Q11") (pin "2") (pinfunction "S_2") (pintype "passive"))
      (node (ref "Q11") (pin "3") (pinfunction "S_3") (pintype "passive"))
      (node (ref "R107") (pin "2") (pinfunction "2_2") (pintype "passive"))
      (node (ref "U3") (pin "12") (pinfunction "SPB_12") (pintype "input"))
    )
    (net (code "32") (name "/SPC2") (class "Default")
      (node (ref "C56") (pin "2") (pinfunction "2_2") (pintype "passive"))
      (node (ref "C66") (pin "1") (pinfunction "1_1") (pintype "passive"))
      (node (ref "Q12") (pin "1") (pinfunction "S_1") (pintype "passive"))
      (node (ref "Q12") (pin "2") (pinfunction "S_2") (pintype "passive"))
      (node (ref "Q12") (pin "3") (pinfunction "S_3") (pintype "passive"))
      (node (ref "R108") (pin "2") (pinfunction "2_2") (pintype "passive"))
      (node (ref "U3") (pin "19") (pinfunction "SPC_19") (pintype "input"))
    )
    (net (code "33") (name "/VDRAIN") (class "Default")
      (node (ref "C97") (pin "1") (pinfunction "1_1") (pintype "passive"))
      (node (ref "NT8") (pin "1") (pinfunction "1_1") (pintype "passive"))
      (node (ref "U3") (pin "4") (pinfunction "VDRAIN_4") (pintype "input"))
    )
    (net (code "34") (name "/VSENA2") (class "Default")
      (node (ref "C77") (pin "2") (pinfunction "2_2") (pintype "passive"))
      (node (ref "J12") (pin "5") (pinfunction "5_5") (pintype "passive"))
      (node (ref "R72") (pin "1") (pinfunction "1_1") (pintype "passive"))
      (node (ref "R86") (pin "2") (pinfunction "2_2") (pintype "passive"))
      (node (ref "U5") (pin "1") (pinfunction "D1+_1") (pintype "passive"))
    )
    (net (code "35") (name "/VSENB2") (class "Default")
      (node (ref "C74") (pin "2") (pinfunction "2_2") (pintype "passive"))
      (node (ref "J12") (pin "7") (pinfunction "7_7") (pintype "passive"))
      (node (ref "R73") (pin "1") (pinfunction "1_1") (pintype "passive"))
      (node (ref "R77") (pin "2") (pinfunction "2_2") (pintype "passive"))
      (node (ref "U5") (pin "2") (pinfunction "D1-_2") (pintype "passive"))
    )
    (net (code "36") (name "/VSENC2") (class "Default")
      (node (ref "C75") (pin "2") (pinfunction "2_2") (pintype "passive"))
      (node (ref "J12") (pin "9") (pinfunction "9_9") (pintype "passive"))
      (node (ref "R75") (pin "1") (pinfunction "1_1") (pintype "passive"))
      (node (ref "R78") (pin "2") (pinfunction "2_2") (pintype "passive"))
      (node (ref "U5") (pin "4") (pinfunction "D2+_4") (pintype "passive"))
    )
    (net (code "37") (name "/VSENVM") (class "Default")
      (node (ref "J12") (pin "4") (pinfunction "4_4") (pintype "passive"))
      (node (ref "U5") (pin "5") (pinfunction "D2-_5") (pintype "passive"))
    )
    (net (code "38") (name "/nFAULT2") (class "Default")
      (node (ref "J12") (pin "16") (pinfunction "16_16") (pintype "passive"))
      (node (ref "R54") (pin "1") (pinfunction "1_1") (pintype "passive"))
      (node (ref "R99") (pin "1") (pinfunction "1_1") (pintype "passive"))
      (node (ref "U3") (pin "26") (pinfunction "FAULT_N_26") (pintype "open_collector"))
    )
    (net (code "39") (name "24V") (class "Default")
      (node (ref "C133") (pin "2") (pinfunction "2_2") (pintype "passive"))
      (node (ref "C87") (pin "2") (pinfunction "2_2") (pintype "passive"))
      (node (ref "TP19") (pin "1") (pintype "passive"))
      (node (ref "U3") (pin "3") (pinfunction "VM_3") (pintype "power_in"))
    )
    (net (code "40") (name "DRV_SCLK") (class "Default")
      (node (ref "J12") (pin "14") (pinfunction "14_14") (pintype "passive"))
      (node (ref "U3") (pin "29") (pinfunction "SCLK_29") (pintype "input"))
    )
    (net (code "41") (name "DRV_SDI") (class "Default")
      (node (ref "J13") (pin "11") (pinfunction "11_11") (pintype "passive"))
      (node (ref "U3") (pin "28") (pinfunction "SDI_28") (pintype "input"))
    )
    (net (code "42") (name "DRV_SDO") (class "Default")
      (node (ref "J13") (pin "13") (pinfunction "13_13") (pintype "passive"))
      (node (ref "U3") (pin "27") (pinfunction "SDO_27") (pintype "passive"))
    )
    (net (code "43") (name "DRV_nSCS2") (class "Default")
      (node (ref "J13") (pin "17") (pinfunction "17_17") (pintype "passive"))
      (node (ref "U3") (pin "30") (pinfunction "SCS_N_30") (pintype "input"))
    )
    (net (code "44") (name "GND") (class "Default")
      (node (ref "C133") (pin "1") (pinfunction "1_1") (pintype "passive"))
      (node (ref "C137") (pin "1") (pinfunction "1_1") (pintype "passive"))
      (node (ref "C140") (pin "1") (pinfunction "1_1") (pintype "passive"))
      (node (ref "C175") (pin "2") (pinfunction "2_2") (pintype "passive"))
      (node (ref "C48") (pin "1") (pinfunction "1_1") (pintype "passive"))
      (node (ref "C49") (pin "1") (pinfunction "1_1") (pintype "passive"))
      (node (ref "C50") (pin "1") (pinfunction "1_1") (pintype "passive"))
      (node (ref "C74") (pin "1") (pinfunction "1_1") (pintype "passive"))
      (node (ref "C75") (pin "1") (pinfunction "1_1") (pintype "passive"))
      (node (ref "C77") (pin "1") (pinfunction "1_1") (pintype "passive"))
      (node (ref "C82") (pin "1") (pinfunction "1_1") (pintype "passive"))
      (node (ref "C83") (pin "1") (pinfunction "1_1") (pintype "passive"))
      (node (ref "C87") (pin "1") (pinfunction "1_1") (pintype "passive"))
      (node (ref "C91") (pin "1") (pinfunction "1_1") (pintype "passive"))
      (node (ref "NT12") (pin "2") (pinfunction "2_2") (pintype "passive"))
      (node (ref "NT13") (pin "2") (pinfunction "2_2") (pintype "passive"))
      (node (ref "NT14") (pin "2") (pinfunction "2_2") (pintype "passive"))
      (node (ref "R105") (pin "1") (pinfunction "1_1") (pintype "passive"))
      (node (ref "R107") (pin "1") (pinfunction "1_1") (pintype "passive"))
      (node (ref "R108") (pin "1") (pinfunction "1_1") (pintype "passive"))
      (node (ref "R77") (pin "1") (pinfunction "1_1") (pintype "passive"))
      (node (ref "R78") (pin "1") (pinfunction "1_1") (pintype "passive"))
      (node (ref "R86") (pin "1") (pinfunction "1_1") (pintype "passive"))
      (node (ref "TP30") (pin "1") (pintype "passive"))
      (node (ref "TP31") (pin "1") (pintype "passive"))
      (node (ref "TP32") (pin "1") (pintype "passive"))
      (node (ref "TP35") (pin "1") (pinfunction "1_1") (pintype "passive"))
      (node (ref "TP35") (pin "2") (pinfunction "2_2") (pintype "passive"))
      (node (ref "TP36") (pin "1") (pinfunction "1_1") (pintype "passive"))
      (node (ref "TP36") (pin "2") (pinfunction "2_2") (pintype "passive"))
      (node (ref "U3") (pin "25") (pinfunction "AGND_25") (pintype "power_in"))
      (node (ref "U3") (pin "39") (pinfunction "PGND_39") (pintype "power_in"))
      (node (ref "U3") (pin "41") (pinfunction "PAD_41") (pintype "power_in"))
      (node (ref "U5") (pin "3") (pinfunction "GND_3") (pintype "power_in"))
      (node (ref "U5") (pin "8") (pinfunction "GND_8") (pintype "power_in"))
    )
    (net (code "45") (name "Net-(D3-C)") (class "Default")
      (node (ref "D3") (pin "1") (pinfunction "C_1") (pintype "passive"))
      (node (ref "R54") (pin "2") (pinfunction "2_2") (pintype "passive"))
    )
    (net (code "46") (name "Net-(U3-CPH)") (class "Default")
      (node (ref "C35") (pin "2") (pinfunction "2_2") (pintype "passive"))
      (node (ref "U3") (pin "2") (pinfunction "CPH_2") (pintype "passive"))
    )
    (net (code "47") (name "Net-(U3-CPL)") (class "Default")
      (node (ref "C35") (pin "1") (pinfunction "1_1") (pintype "passive"))
      (node (ref "U3") (pin "1") (pinfunction "CPL_1") (pintype "passive"))
    )
    (net (code "48") (name "Net-(U3-VCP)") (class "Default")
      (node (ref "C97") (pin "2") (pinfunction "2_2") (pintype "passive"))
      (node (ref "TP23") (pin "1") (pintype "passive"))
      (node (ref "U3") (pin "5") (pinfunction "VCP_5") (pintype "power_in"))
    )
    (net (code "49") (name "Net-(U3-VGLS)") (class "Default")
      (node (ref "C175") (pin "1") (pinfunction "1_1") (pintype "passive"))
      (node (ref "U3") (pin "40") (pinfunction "VGLS_40") (pintype "power_in"))
    )
    (net (code "50") (name "VDD_3V3") (class "Default")
      (node (ref "D3") (pin "2") (pinfunction "A_2") (pintype "passive"))
      (node (ref "R99") (pin "2") (pinfunction "2_2") (pintype "passive"))
    )
    (net (code "51") (name "VDD_A3V3") (class "Default")
      (node (ref "C137") (pin "2") (pinfunction "2_2") (pintype "passive"))
      (node (ref "U3") (pin "24") (pinfunction "VREF_24") (pintype "input"))
    )
    (net (code "52") (name "VM") (class "Default")
      (node (ref "C48") (pin "2") (pinfunction "2_2") (pintype "passive"))
      (node (ref "C49") (pin "2") (pinfunction "2_2") (pintype "passive"))
      (node (ref "C50") (pin "2") (pinfunction "2_2") (pintype "passive"))
      (node (ref "NT8") (pin "2") (pinfunction "2_2") (pintype "passive"))
      (node (ref "Q7") (pin "5") (pinfunction "D_5") (pintype "passive"))
      (node (ref "Q7") (pin "6") (pinfunction "D_6") (pintype "passive"))
      (node (ref "Q7") (pin "7") (pinfunction "D_7") (pintype "passive"))
      (node (ref "Q7") (pin "8") (pinfunction "D_8") (pintype "passive"))
      (node (ref "Q7") (pin "9") (pinfunction "D_9") (pintype "passive"))
      (node (ref "Q8") (pin "5") (pinfunction "D_5") (pintype "passive"))
      (node (ref "Q8") (pin "6") (pinfunction "D_6") (pintype "passive"))
      (node (ref "Q8") (pin "7") (pinfunction "D_7") (pintype "passive"))
      (node (ref "Q8") (pin "8") (pinfunction "D_8") (pintype "passive"))
      (node (ref "Q8") (pin "9") (pinfunction "D_9") (pintype "passive"))
      (node (ref "Q9") (pin "5") (pinfunction "D_5") (pintype "passive"))
      (node (ref "Q9") (pin "6") (pinfunction "D_6") (pintype "passive"))
      (node (ref "Q9") (pin "7") (pinfunction "D_7") (pintype "passive"))
      (node (ref "Q9") (pin "8") (pinfunction "D_8") (pintype "passive"))
      (node (ref "Q9") (pin "9") (pinfunction "D_9") (pintype "passive"))
    )
    (net (code "53") (name "unconnected-(J12-Pad1)") (class "Default")
      (node (ref "J12") (pin "1") (pinfunction "1_1") (pintype "passive+no_connect"))
    )
    (net (code "54") (name "unconnected-(J12-Pad2)") (class "Default")
      (node (ref "J12") (pin "2") (pinfunction "2_2") (pintype "passive+no_connect"))
    )
    (net (code "55") (name "unconnected-(J12-Pad3)") (class "Default")
      (node (ref "J12") (pin "3") (pinfunction "3_3") (pintype "passive+no_connect"))
    )
    (net (code "56") (name "unconnected-(J12-Pad6)") (class "Default")
      (node (ref "J12") (pin "6") (pinfunction "6_6") (pintype "passive+no_connect"))
    )
    (net (code "57") (name "unconnected-(J12-Pad8)") (class "Default")
      (node (ref "J12") (pin "8") (pinfunction "8_8") (pintype "passive+no_connect"))
    )
    (net (code "58") (name "unconnected-(J12-Pad12)") (class "Default")
      (node (ref "J12") (pin "12") (pinfunction "12_12") (pintype "passive+no_connect"))
    )
    (net (code "59") (name "unconnected-(J12-Pad17)") (class "Default")
      (node (ref "J12") (pin "17") (pinfunction "17_17") (pintype "passive+no_connect"))
    )
    (net (code "60") (name "unconnected-(J12-Pad18)") (class "Default")
      (node (ref "J12") (pin "18") (pinfunction "18_18") (pintype "passive+no_connect"))
    )
    (net (code "61") (name "unconnected-(J12-Pad19)") (class "Default")
      (node (ref "J12") (pin "19") (pinfunction "19_19") (pintype "passive+no_connect"))
    )
    (net (code "62") (name "unconnected-(J12-Pad20)") (class "Default")
      (node (ref "J12") (pin "20") (pinfunction "20_20") (pintype "passive+no_connect"))
    )
    (net (code "63") (name "unconnected-(J13-Pad1)") (class "Default")
      (node (ref "J13") (pin "1") (pinfunction "1_1") (pintype "passive+no_connect"))
    )
    (net (code "64") (name "unconnected-(J13-Pad3)") (class "Default")
      (node (ref "J13") (pin "3") (pinfunction "3_3") (pintype "passive+no_connect"))
    )
    (net (code "65") (name "unconnected-(J13-Pad5)") (class "Default")
      (node (ref "J13") (pin "5") (pinfunction "5_5") (pintype "passive+no_connect"))
    )
    (net (code "66") (name "unconnected-(J13-Pad7)") (class "Default")
      (node (ref "J13") (pin "7") (pinfunction "7_7") (pintype "passive+no_connect"))
    )
    (net (code "67") (name "unconnected-(J13-Pad9)") (class "Default")
      (node (ref "J13") (pin "9") (pinfunction "9_9") (pintype "passive+no_connect"))
    )
    (net (code "68") (name "unconnected-(J13-Pad14)") (class "Default")
      (node (ref "J13") (pin "14") (pinfunction "14_14") (pintype "passive+no_connect"))
    )
    (net (code "69") (name "unconnected-(J13-Pad15)") (class "Default")
      (node (ref "J13") (pin "15") (pinfunction "15_15") (pintype "passive+no_connect"))
    )
    (net (code "70") (name "unconnected-(J13-Pad16)") (class "Default")
      (node (ref "J13") (pin "16") (pinfunction "16_16") (pintype "passive+no_connect"))
    )
    (net (code "71") (name "unconnected-(J13-Pad18)") (class "Default")
      (node (ref "J13") (pin "18") (pinfunction "18_18") (pintype "passive+no_connect"))
    )
    (net (code "72") (name "unconnected-(J13-Pad19)") (class "Default")
      (node (ref "J13") (pin "19") (pinfunction "19_19") (pintype "passive+no_connect"))
    )
    (net (code "73") (name "unconnected-(J13-Pad20)") (class "Default")
      (node (ref "J13") (pin "20") (pinfunction "20_20") (pintype "passive+no_connect"))
    )
    (net (code "74") (name "unconnected-(U5-NC-Pad6)") (class "Default")
      (node (ref "U5") (pin "6") (pinfunction "NC_6") (pintype "passive+no_connect"))
    )
    (net (code "75") (name "unconnected-(U5-NC-Pad7)") (class "Default")
      (node (ref "U5") (pin "7") (pinfunction "NC_7") (pintype "passive+no_connect"))
    )
    (net (code "76") (name "unconnected-(U5-NC-Pad9)") (class "Default")
      (node (ref "U5") (pin "9") (pinfunction "NC_9") (pintype "passive+no_connect"))
    )
    (net (code "77") (name "unconnected-(U5-NC-Pad10)") (class "Default")
      (node (ref "U5") (pin "10") (pinfunction "NC_10") (pintype "passive+no_connect"))
    )
  )
)
